# Front_right_lamp_v2.net
KiCad netlist of a schematic drawn in EAGLE
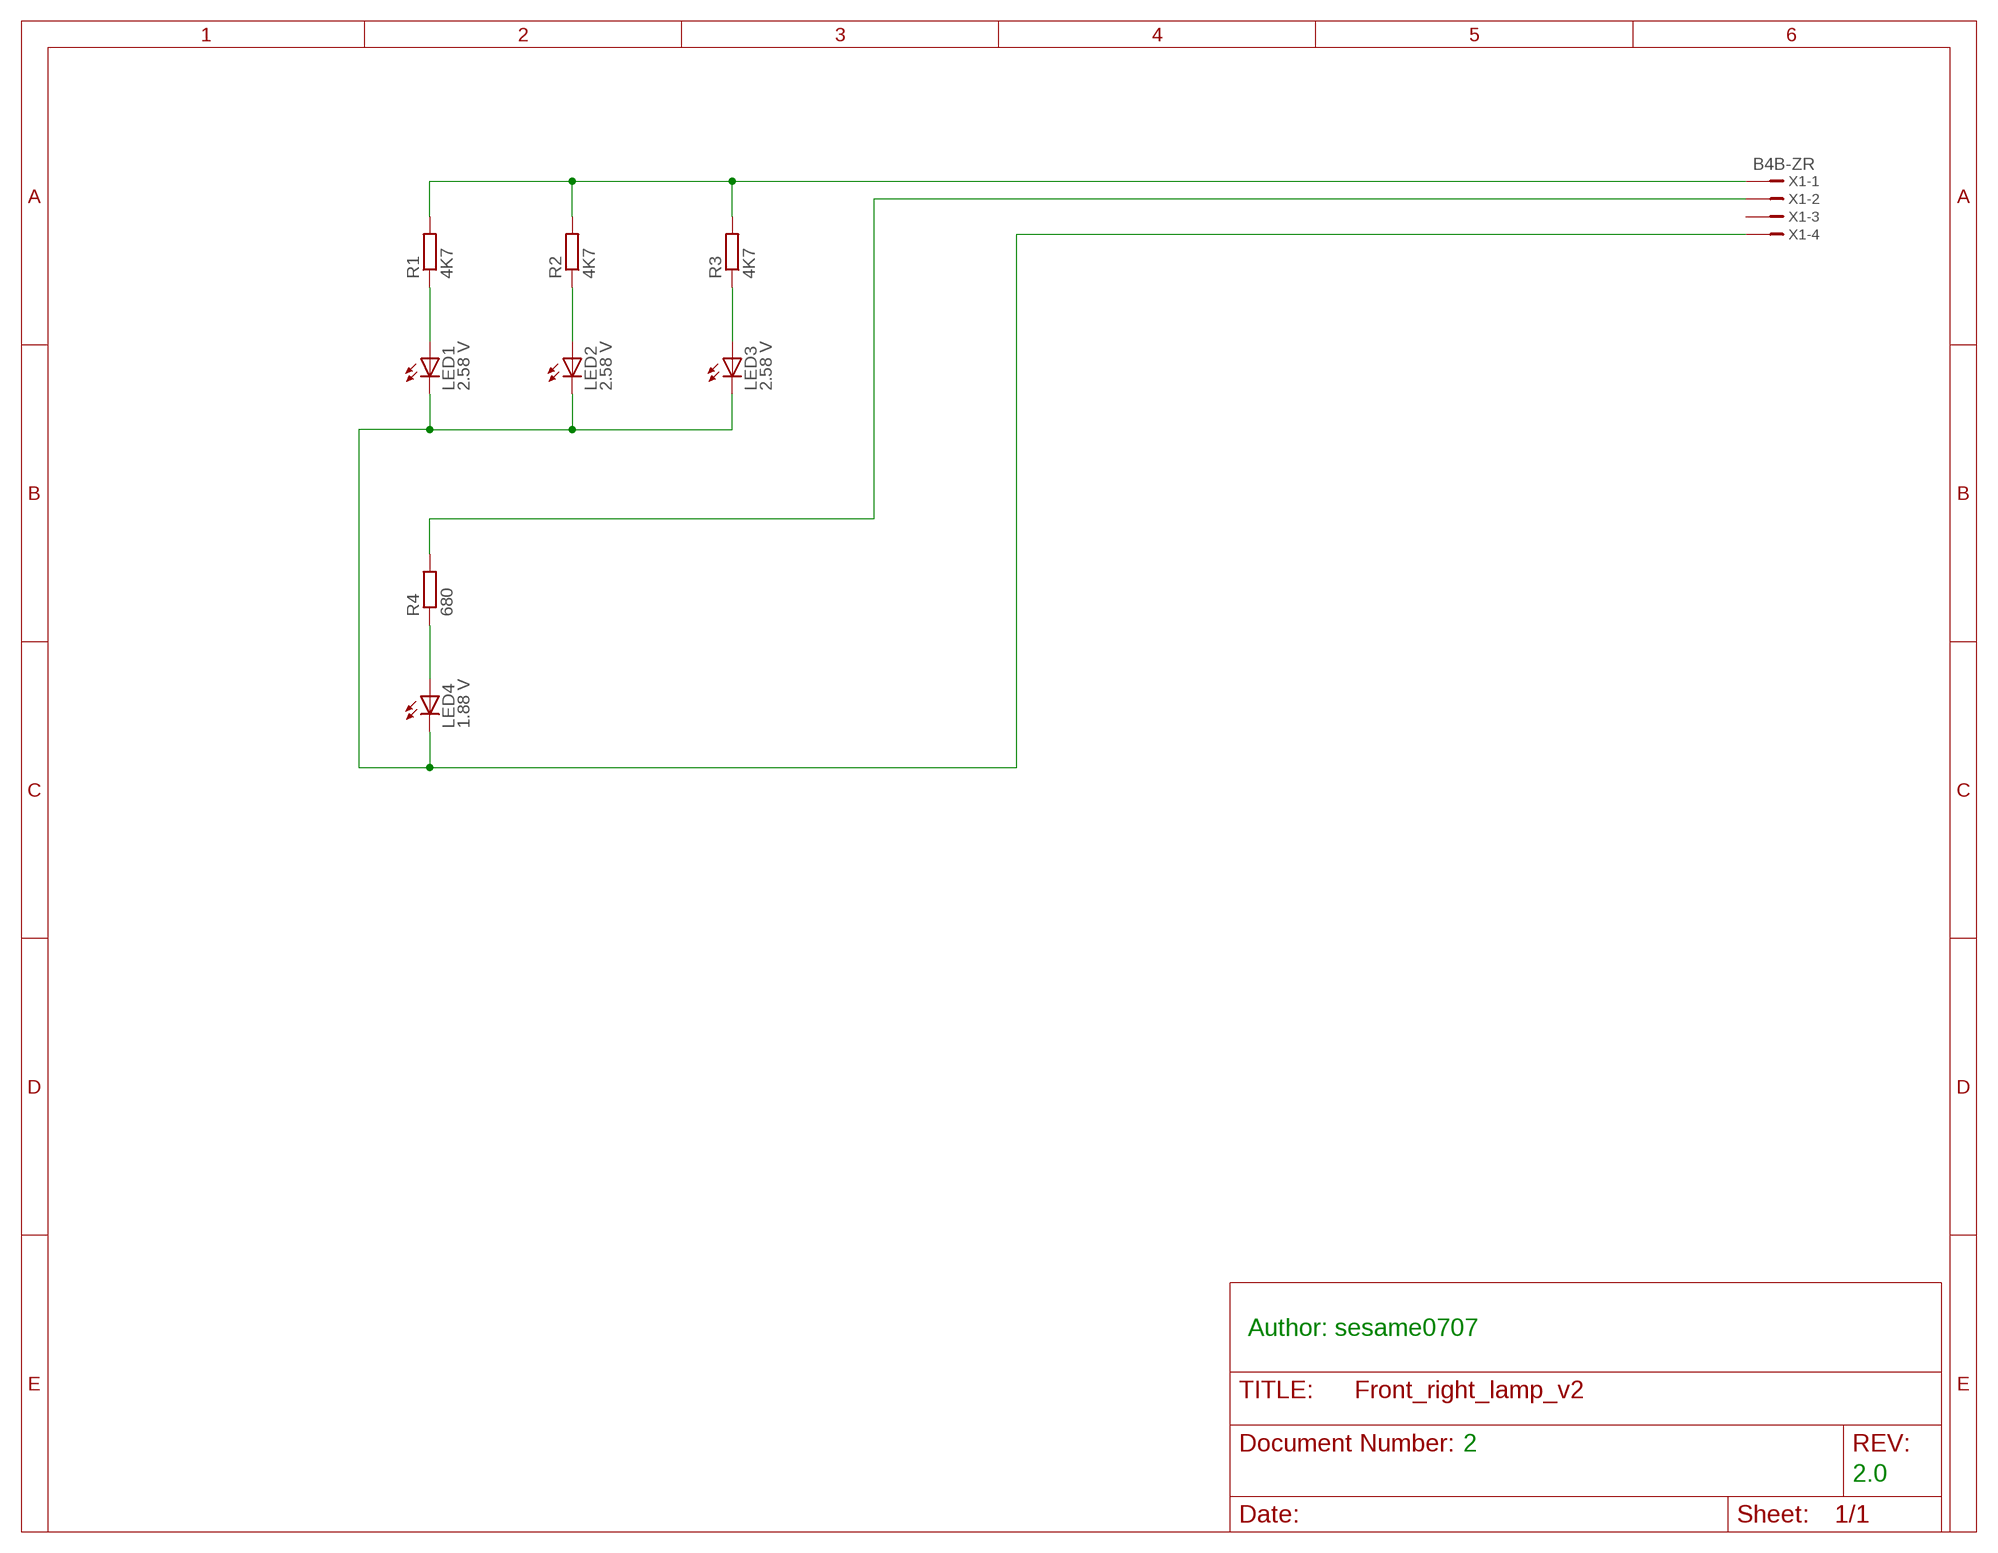
[diagram p0: schematic, sheet 1]

(export (version "E")
  (design (tool "Eeschema 10.0.6"))
  (components
    (comp (ref "LED1")
      (value "2.58 V")
      (footprint "eagle-import:LED5MM")
      (libsource (lib "eagle-import") (part "LED5MM"))
    )
    (comp (ref "LED2")
      (value "2.58 V")
      (footprint "eagle-import:LED5MM")
      (libsource (lib "eagle-import") (part "LED5MM"))
    )
    (comp (ref "LED3")
      (value "2.58 V")
      (footprint "eagle-import:LED5MM")
      (libsource (lib "eagle-import") (part "LED5MM"))
    )
    (comp (ref "LED4")
      (value "1.88 V")
      (footprint "eagle-import:LED5MM")
      (libsource (lib "eagle-import") (part "LED5MM"))
    )
    (comp (ref "R1")
      (value "4K7")
      (footprint "eagle-import:0204V")
      (libsource (lib "eagle-import") (part "R-EU_0204/2V"))
    )
    (comp (ref "R2")
      (value "4K7")
      (footprint "eagle-import:0204V")
      (libsource (lib "eagle-import") (part "R-EU_0204/2V"))
    )
    (comp (ref "R3")
      (value "4K7")
      (footprint "eagle-import:0204V")
      (libsource (lib "eagle-import") (part "R-EU_0204/2V"))
    )
    (comp (ref "R4")
      (value "680")
      (footprint "eagle-import:0204V")
      (libsource (lib "eagle-import") (part "R-EU_0204/2V"))
    )
    (comp (ref "X1")
      (value "B4B-ZR")
      (footprint "eagle-import:B4B-ZR")
      (fields (field (name "MF") "FARNELL") (field (name "MPN") "B4B-ZR(LF)(SN)"))
      (libsource (lib "eagle-import") (part "?4B-ZRB"))
    )
  )
  (nets
    (net (code "1") (name "Net-(LED1-C)") (class "Default")
      (node (ref "LED1") (pin "K") (pinfunction "C_K") (pintype "passive"))
      (node (ref "LED2") (pin "K") (pinfunction "C_K") (pintype "passive"))
      (node (ref "LED3") (pin "K") (pinfunction "C_K") (pintype "passive"))
      (node (ref "LED4") (pin "K") (pinfunction "C_K") (pintype "passive"))
      (node (ref "X1") (pin "4") (pinfunction "1_4") (pintype "passive"))
    )
    (net (code "2") (name "Net-(LED1-PadA)") (class "Default")
      (node (ref "LED1") (pin "A") (pinfunction "A_A") (pintype "passive"))
      (node (ref "R1") (pin "1") (pinfunction "1_1") (pintype "passive"))
    )
    (net (code "3") (name "Net-(LED2-PadA)") (class "Default")
      (node (ref "LED2") (pin "A") (pinfunction "A_A") (pintype "passive"))
      (node (ref "R2") (pin "1") (pinfunction "1_1") (pintype "passive"))
    )
    (net (code "4") (name "Net-(LED3-PadA)") (class "Default")
      (node (ref "LED3") (pin "A") (pinfunction "A_A") (pintype "passive"))
      (node (ref "R3") (pin "1") (pinfunction "1_1") (pintype "passive"))
    )
    (net (code "5") (name "Net-(LED4-PadA)") (class "Default")
      (node (ref "LED4") (pin "A") (pinfunction "A_A") (pintype "passive"))
      (node (ref "R4") (pin "1") (pinfunction "1_1") (pintype "passive"))
    )
    (net (code "6") (name "Net-(R1-Pad2)") (class "Default")
      (node (ref "R1") (pin "2") (pinfunction "2_2") (pintype "passive"))
      (node (ref "R2") (pin "2") (pinfunction "2_2") (pintype "passive"))
      (node (ref "R3") (pin "2") (pinfunction "2_2") (pintype "passive"))
      (node (ref "X1") (pin "1") (pinfunction "1_1") (pintype "passive"))
    )
    (net (code "7") (name "Net-(X1B-1)") (class "Default")
      (node (ref "R4") (pin "2") (pinfunction "2_2") (pintype "passive"))
      (node (ref "X1") (pin "2") (pinfunction "1_2") (pintype "passive"))
    )
    (net (code "8") (name "unconnected-(X1C-1-Pad3)") (class "Default")
      (node (ref "X1") (pin "3") (pinfunction "1_3") (pintype "passive"))
    )
  )
)
